# USB_Multiplicator.net
KiCad netlist of a schematic drawn in EAGLE
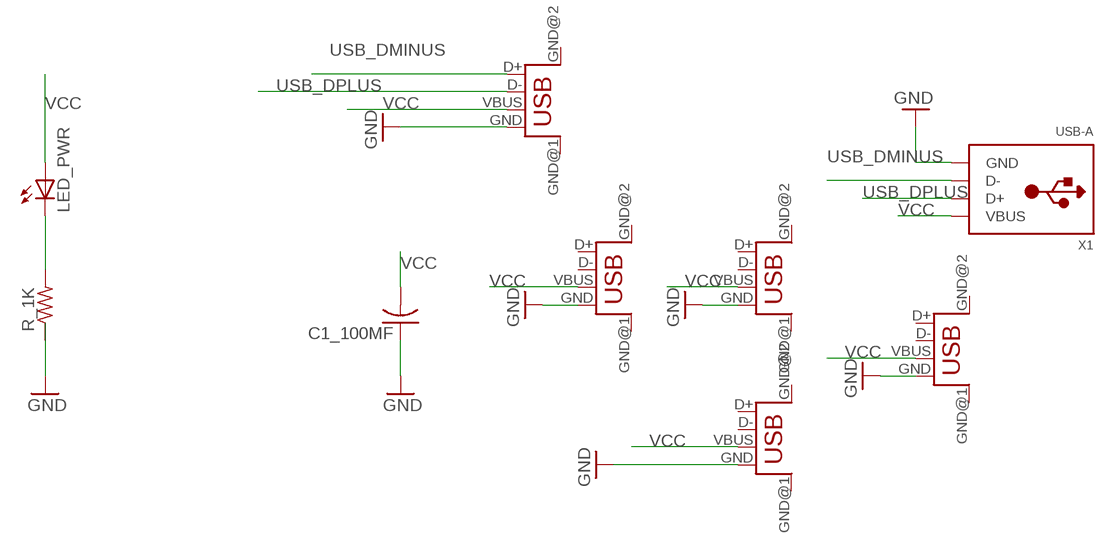
[diagram p0: schematic, sheet 1]

(export (version "E")
  (design (tool "Eeschema 10.0.6"))
  (components
    (comp (ref "C1_100MF")
      (value "C-US025-030X050")
      (footprint "eagle-import:C025-030X050")
      (libsource (lib "eagle-import") (part "C-US025-030X050"))
    )
    (comp (ref "LED_PWR")
      (value "LEDSMT1206")
      (footprint "eagle-import:1206")
      (libsource (lib "eagle-import") (part "LEDSMT1206"))
    )
    (comp (ref "R_1K")
      (value "R-US_R1206")
      (footprint "eagle-import:R1206")
      (libsource (lib "eagle-import") (part "R-US_R1206"))
    )
    (comp (ref "USB_OUT_2")
      (value "USB")
      (footprint "eagle-import:USB-FEMALE-A-PTH")
      (libsource (lib "eagle-import") (part "USB"))
    )
    (comp (ref "USB_OUT_3")
      (value "USB")
      (footprint "eagle-import:USB-FEMALE-A-PTH")
      (libsource (lib "eagle-import") (part "USB"))
    )
    (comp (ref "USB_OUT_4")
      (value "USB")
      (footprint "eagle-import:USB-FEMALE-A-PTH")
      (libsource (lib "eagle-import") (part "USB"))
    )
    (comp (ref "USB_OUT_5")
      (value "USB")
      (footprint "eagle-import:USB-FEMALE-A-PTH")
      (libsource (lib "eagle-import") (part "USB"))
    )
    (comp (ref "USB_OUT_WITH_DATA_1")
      (value "USB")
      (footprint "eagle-import:USB-FEMALE-A-PTH")
      (libsource (lib "eagle-import") (part "USB"))
    )
    (comp (ref "X1")
      (value "USB-A")
      (footprint "eagle-import:MOLEX_480371000")
      (libsource (lib "eagle-import") (part "USB-A"))
    )
  )
  (nets
    (net (code "1") (name "/USB_DMINUS") (class "Default")
      (node (ref "USB_OUT_WITH_DATA_1") (pin "D+") (pinfunction "D+_D+") (pintype "bidirectional"))
      (node (ref "X1") (pin "2") (pinfunction "D-_2") (pintype "bidirectional"))
    )
    (net (code "2") (name "/USB_DPLUS") (class "Default")
      (node (ref "USB_OUT_WITH_DATA_1") (pin "D-") (pinfunction "D-_D-") (pintype "bidirectional"))
      (node (ref "X1") (pin "3") (pinfunction "D+_3") (pintype "bidirectional"))
    )
    (net (code "3") (name "/VCC") (class "Default")
      (node (ref "C1_100MF") (pin "2") (pinfunction "2_2") (pintype "passive"))
      (node (ref "LED_PWR") (pin "A") (pinfunction "A_A") (pintype "passive"))
      (node (ref "USB_OUT_2") (pin "VBUS") (pinfunction "VBUS_VBUS") (pintype "bidirectional"))
      (node (ref "USB_OUT_3") (pin "VBUS") (pinfunction "VBUS_VBUS") (pintype "bidirectional"))
      (node (ref "USB_OUT_4") (pin "VBUS") (pinfunction "VBUS_VBUS") (pintype "bidirectional"))
      (node (ref "USB_OUT_5") (pin "VBUS") (pinfunction "VBUS_VBUS") (pintype "bidirectional"))
      (node (ref "USB_OUT_WITH_DATA_1") (pin "VBUS") (pinfunction "VBUS_VBUS") (pintype "bidirectional"))
      (node (ref "X1") (pin "1") (pinfunction "VBUS_1") (pintype "power_in"))
    )
    (net (code "4") (name "GND") (class "Default")
      (node (ref "C1_100MF") (pin "1") (pinfunction "1_1") (pintype "passive"))
      (node (ref "R_1K") (pin "1") (pinfunction "1_1") (pintype "passive"))
      (node (ref "USB_OUT_2") (pin "GND") (pinfunction "GND_GND") (pintype "bidirectional"))
      (node (ref "USB_OUT_3") (pin "GND") (pinfunction "GND_GND") (pintype "bidirectional"))
      (node (ref "USB_OUT_4") (pin "GND") (pinfunction "GND_GND") (pintype "bidirectional"))
      (node (ref "USB_OUT_5") (pin "GND") (pinfunction "GND_GND") (pintype "bidirectional"))
      (node (ref "USB_OUT_WITH_DATA_1") (pin "GND") (pinfunction "GND_GND") (pintype "bidirectional"))
      (node (ref "X1") (pin "4") (pinfunction "GND_4") (pintype "power_in"))
    )
    (net (code "5") (name "Net-(LED_PWR-PadC)") (class "Default")
      (node (ref "LED_PWR") (pin "C") (pinfunction "C_C") (pintype "passive"))
      (node (ref "R_1K") (pin "2") (pinfunction "2_2") (pintype "passive"))
    )
    (net (code "6") (name "unconnected-(USB_OUT_2-GND-PadGND@1)") (class "Default")
      (node (ref "USB_OUT_2") (pin "GND@1") (pinfunction "GND_GND@1") (pintype "bidirectional"))
    )
    (net (code "7") (name "unconnected-(USB_OUT_2-GND-PadGND@2)") (class "Default")
      (node (ref "USB_OUT_2") (pin "GND@2") (pinfunction "GND_GND@2") (pintype "bidirectional"))
    )
    (net (code "8") (name "unconnected-(USB_OUT_2-PadD+)") (class "Default")
      (node (ref "USB_OUT_2") (pin "D+") (pinfunction "D+_D+") (pintype "bidirectional"))
    )
    (net (code "9") (name "unconnected-(USB_OUT_2-PadD-)") (class "Default")
      (node (ref "USB_OUT_2") (pin "D-") (pinfunction "D-_D-") (pintype "bidirectional"))
    )
    (net (code "10") (name "unconnected-(USB_OUT_3-GND-PadGND@1)") (class "Default")
      (node (ref "USB_OUT_3") (pin "GND@1") (pinfunction "GND_GND@1") (pintype "bidirectional"))
    )
    (net (code "11") (name "unconnected-(USB_OUT_3-GND-PadGND@2)") (class "Default")
      (node (ref "USB_OUT_3") (pin "GND@2") (pinfunction "GND_GND@2") (pintype "bidirectional"))
    )
    (net (code "12") (name "unconnected-(USB_OUT_3-PadD+)") (class "Default")
      (node (ref "USB_OUT_3") (pin "D+") (pinfunction "D+_D+") (pintype "bidirectional"))
    )
    (net (code "13") (name "unconnected-(USB_OUT_3-PadD-)") (class "Default")
      (node (ref "USB_OUT_3") (pin "D-") (pinfunction "D-_D-") (pintype "bidirectional"))
    )
    (net (code "14") (name "unconnected-(USB_OUT_4-GND-PadGND@1)") (class "Default")
      (node (ref "USB_OUT_4") (pin "GND@1") (pinfunction "GND_GND@1") (pintype "bidirectional"))
    )
    (net (code "15") (name "unconnected-(USB_OUT_4-GND-PadGND@2)") (class "Default")
      (node (ref "USB_OUT_4") (pin "GND@2") (pinfunction "GND_GND@2") (pintype "bidirectional"))
    )
    (net (code "16") (name "unconnected-(USB_OUT_4-PadD+)") (class "Default")
      (node (ref "USB_OUT_4") (pin "D+") (pinfunction "D+_D+") (pintype "bidirectional"))
    )
    (net (code "17") (name "unconnected-(USB_OUT_4-PadD-)") (class "Default")
      (node (ref "USB_OUT_4") (pin "D-") (pinfunction "D-_D-") (pintype "bidirectional"))
    )
    (net (code "18") (name "unconnected-(USB_OUT_5-GND-PadGND@1)") (class "Default")
      (node (ref "USB_OUT_5") (pin "GND@1") (pinfunction "GND_GND@1") (pintype "bidirectional"))
    )
    (net (code "19") (name "unconnected-(USB_OUT_5-GND-PadGND@2)") (class "Default")
      (node (ref "USB_OUT_5") (pin "GND@2") (pinfunction "GND_GND@2") (pintype "bidirectional"))
    )
    (net (code "20") (name "unconnected-(USB_OUT_5-PadD+)") (class "Default")
      (node (ref "USB_OUT_5") (pin "D+") (pinfunction "D+_D+") (pintype "bidirectional"))
    )
    (net (code "21") (name "unconnected-(USB_OUT_5-PadD-)") (class "Default")
      (node (ref "USB_OUT_5") (pin "D-") (pinfunction "D-_D-") (pintype "bidirectional"))
    )
    (net (code "22") (name "unconnected-(USB_OUT_WITH_DATA_1-GND-PadGND@1)") (class "Default")
      (node (ref "USB_OUT_WITH_DATA_1") (pin "GND@1") (pinfunction "GND_GND@1") (pintype "bidirectional"))
    )
    (net (code "23") (name "unconnected-(USB_OUT_WITH_DATA_1-GND-PadGND@2)") (class "Default")
      (node (ref "USB_OUT_WITH_DATA_1") (pin "GND@2") (pinfunction "GND_GND@2") (pintype "bidirectional"))
    )
  )
)
